# esp32Pinout.net
KiCad netlist of a schematic drawn in Altium Designer
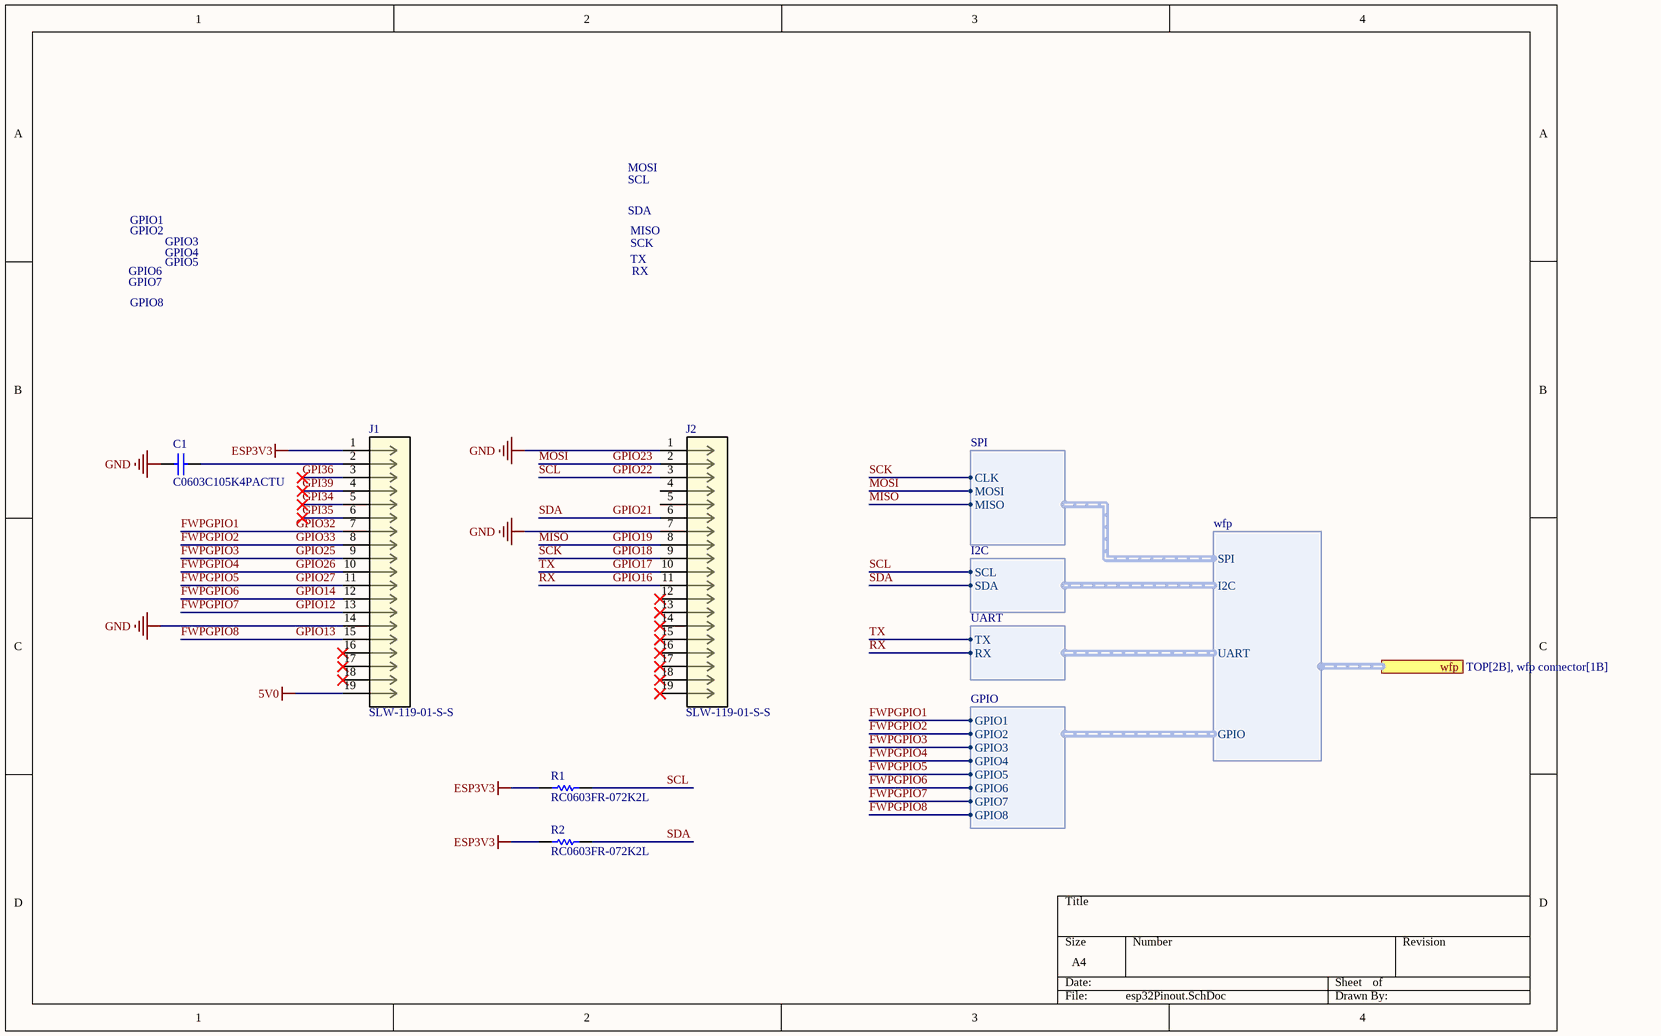
[diagram p0: esp32Pinout.SchDoc]

(export (version "E")
  (design (tool "Eeschema 10.0.6"))
  (components
    (comp (ref "C1")
      (value "C0603C105K4PACTU")
      (footprint "CAPC1608X90X35NL15T15")
      (fields (field (name "MANUFACTURER") "Kemet"))
      (libsource (lib "Altium Content Vault") (part "CAP"))
    )
    (comp (ref "J1")
      (value "SLW-119-01-S-S")
      (footprint "CON19_1X19_TU_SLW_SAI")
      (description "No Description Available")
      (libsource (lib "SLW-119-01-S-S") (part "SLW-119-01-S-S"))
    )
    (comp (ref "J2")
      (value "SLW-119-01-S-S")
      (footprint "CON19_1X19_TU_SLW_SAI")
      (description "No Description Available")
      (libsource (lib "SLW-119-01-S-S") (part "SLW-119-01-S-S"))
    )
    (comp (ref "R1")
      (value "RC0603FR-072K2L")
      (footprint "RESC1608X55X25LL10T15")
      (fields (field (name "TOLERANCE") "1%") (field (name "MANUFACTURER") "Yageo"))
      (libsource (lib "Altium Content Vault") (part "RES-2"))
    )
    (comp (ref "R2")
      (value "RC0603FR-072K2L")
      (footprint "RESC1608X55X25LL10T15")
      (fields (field (name "TOLERANCE") "1%") (field (name "MANUFACTURER") "Yageo"))
      (libsource (lib "Altium Content Vault") (part "RES-2"))
    )
  )
  (nets
    (net (code "6") (name "/FWPGPIO1") (class "Default")
      (node (ref "J1") (pin "7") (pinfunction "7_7") (pintype "passive"))
    )
    (net (code "7") (name "/FWPGPIO2") (class "Default")
      (node (ref "J1") (pin "8") (pinfunction "8_8") (pintype "passive"))
    )
    (net (code "8") (name "/FWPGPIO3") (class "Default")
      (node (ref "J1") (pin "9") (pinfunction "9_9") (pintype "passive"))
    )
    (net (code "9") (name "/FWPGPIO4") (class "Default")
      (node (ref "J1") (pin "10") (pinfunction "10_10") (pintype "passive"))
    )
    (net (code "10") (name "/FWPGPIO5") (class "Default")
      (node (ref "J1") (pin "11") (pinfunction "11_11") (pintype "passive"))
    )
    (net (code "11") (name "/FWPGPIO6") (class "Default")
      (node (ref "J1") (pin "12") (pinfunction "12_12") (pintype "passive"))
    )
    (net (code "12") (name "/FWPGPIO7") (class "Default")
      (node (ref "J1") (pin "13") (pinfunction "13_13") (pintype "passive"))
    )
    (net (code "13") (name "/FWPGPIO8") (class "Default")
      (node (ref "J1") (pin "15") (pinfunction "15_15") (pintype "passive"))
    )
    (net (code "14") (name "/GPI34") (class "Default")
      (node (ref "J1") (pin "5") (pinfunction "5_5") (pintype "passive+no_connect"))
    )
    (net (code "15") (name "/GPI35") (class "Default")
      (node (ref "J1") (pin "6") (pinfunction "6_6") (pintype "passive+no_connect"))
    )
    (net (code "16") (name "/GPI36") (class "Default")
      (node (ref "J1") (pin "3") (pinfunction "3_3") (pintype "passive+no_connect"))
    )
    (net (code "17") (name "/GPI39") (class "Default")
      (node (ref "J1") (pin "4") (pinfunction "4_4") (pintype "passive+no_connect"))
    )
    (net (code "18") (name "/GPIO16") (class "Default")
      (node (ref "J2") (pin "11") (pinfunction "11_11") (pintype "passive"))
    )
    (net (code "19") (name "/GPIO17") (class "Default")
      (node (ref "J2") (pin "10") (pinfunction "10_10") (pintype "passive"))
    )
    (net (code "20") (name "/GPIO18") (class "Default")
      (node (ref "J2") (pin "9") (pinfunction "9_9") (pintype "passive"))
    )
    (net (code "21") (name "/GPIO19") (class "Default")
      (node (ref "J2") (pin "8") (pinfunction "8_8") (pintype "passive"))
    )
    (net (code "22") (name "/GPIO21") (class "Default")
      (node (ref "J2") (pin "6") (pinfunction "6_6") (pintype "passive"))
      (node (ref "R2") (pin "2") (pinfunction "2_2") (pintype "passive"))
    )
    (net (code "23") (name "/GPIO22") (class "Default")
      (node (ref "J2") (pin "3") (pinfunction "3_3") (pintype "passive"))
      (node (ref "R1") (pin "2") (pinfunction "2_2") (pintype "passive"))
    )
    (net (code "24") (name "/GPIO23") (class "Default")
      (node (ref "J2") (pin "2") (pinfunction "2_2") (pintype "passive"))
    )
    (net (code "30") (name "5V0") (class "Default")
      (node (ref "J1") (pin "19") (pinfunction "19_19") (pintype "passive"))
    )
    (net (code "31") (name "ESP3V3") (class "Default")
      (node (ref "J1") (pin "1") (pinfunction "1_1") (pintype "passive"))
      (node (ref "R1") (pin "1") (pinfunction "1_1") (pintype "passive"))
      (node (ref "R2") (pin "1") (pinfunction "1_1") (pintype "passive"))
    )
    (net (code "32") (name "GND") (class "Default")
      (node (ref "C1") (pin "1") (pinfunction "1_1") (pintype "passive"))
      (node (ref "J1") (pin "14") (pinfunction "14_14") (pintype "passive"))
      (node (ref "J2") (pin "1") (pinfunction "1_1") (pintype "passive"))
      (node (ref "J2") (pin "7") (pinfunction "7_7") (pintype "passive"))
    )
    (net (code "33") (name "Net-(C1-Pad2)") (class "Default")
      (node (ref "C1") (pin "2") (pinfunction "2_2") (pintype "passive"))
      (node (ref "J1") (pin "2") (pinfunction "2_2") (pintype "passive"))
    )
    (net (code "34") (name "unconnected-(J1-Pad16)") (class "Default")
      (node (ref "J1") (pin "16") (pinfunction "16_16") (pintype "passive+no_connect"))
    )
    (net (code "35") (name "unconnected-(J1-Pad17)") (class "Default")
      (node (ref "J1") (pin "17") (pinfunction "17_17") (pintype "passive+no_connect"))
    )
    (net (code "36") (name "unconnected-(J1-Pad18)") (class "Default")
      (node (ref "J1") (pin "18") (pinfunction "18_18") (pintype "passive+no_connect"))
    )
    (net (code "37") (name "unconnected-(J2-Pad4)") (class "Default")
      (node (ref "J2") (pin "4") (pinfunction "4_4") (pintype "passive"))
    )
    (net (code "38") (name "unconnected-(J2-Pad5)") (class "Default")
      (node (ref "J2") (pin "5") (pinfunction "5_5") (pintype "passive"))
    )
    (net (code "39") (name "unconnected-(J2-Pad12)") (class "Default")
      (node (ref "J2") (pin "12") (pinfunction "12_12") (pintype "passive+no_connect"))
    )
    (net (code "40") (name "unconnected-(J2-Pad13)") (class "Default")
      (node (ref "J2") (pin "13") (pinfunction "13_13") (pintype "passive+no_connect"))
    )
    (net (code "41") (name "unconnected-(J2-Pad14)") (class "Default")
      (node (ref "J2") (pin "14") (pinfunction "14_14") (pintype "passive+no_connect"))
    )
    (net (code "42") (name "unconnected-(J2-Pad15)") (class "Default")
      (node (ref "J2") (pin "15") (pinfunction "15_15") (pintype "passive+no_connect"))
    )
    (net (code "43") (name "unconnected-(J2-Pad16)") (class "Default")
      (node (ref "J2") (pin "16") (pinfunction "16_16") (pintype "passive+no_connect"))
    )
    (net (code "44") (name "unconnected-(J2-Pad17)") (class "Default")
      (node (ref "J2") (pin "17") (pinfunction "17_17") (pintype "passive+no_connect"))
    )
    (net (code "45") (name "unconnected-(J2-Pad18)") (class "Default")
      (node (ref "J2") (pin "18") (pinfunction "18_18") (pintype "passive+no_connect"))
    )
    (net (code "46") (name "unconnected-(J2-Pad19)") (class "Default")
      (node (ref "J2") (pin "19") (pinfunction "19_19") (pintype "passive+no_connect"))
    )
  )
)
